# LCD-Input_Module.net
KiCad netlist of a schematic drawn in EAGLE
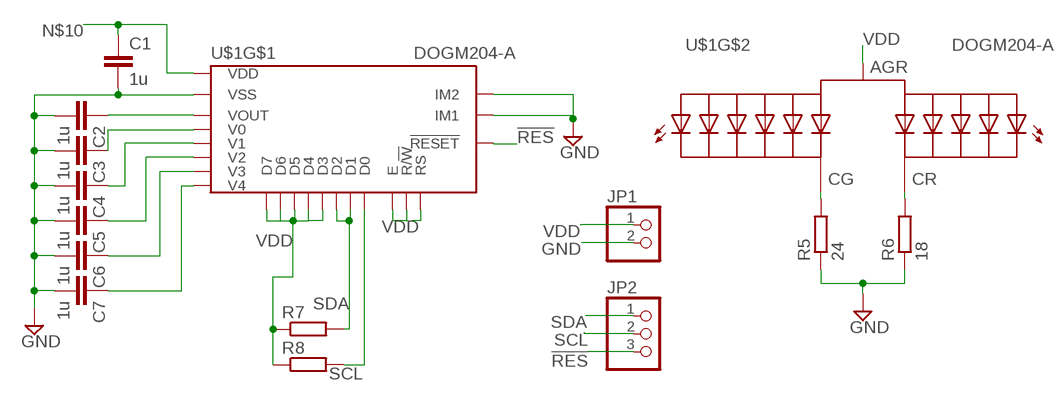
[diagram p0: schematic, sheet 1]
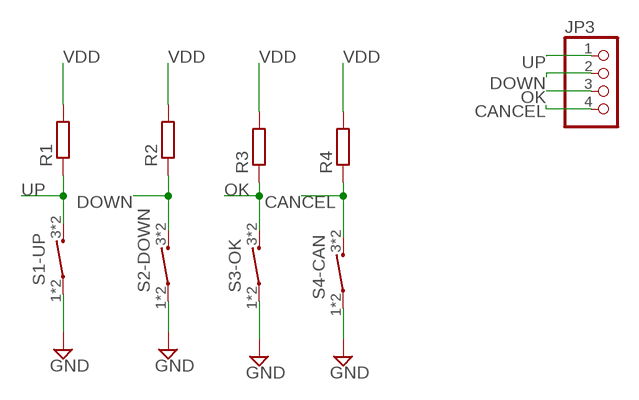
[diagram p1: schematic, sheet 2]

(export (version "E")
  (design (tool "Eeschema 10.0.6"))
  (components
    (comp (ref "JP3")
      (value "PINHD-1X4")
      (footprint "eagle-import:1X04")
      (libsource (lib "eagle-import") (part "PINHD-1X4"))
    )
    (comp (ref "R1")
      (value "R-EU_R0603")
      (footprint "eagle-import:R0603")
      (libsource (lib "eagle-import") (part "R-EU_R0603"))
    )
    (comp (ref "R2")
      (value "R-EU_R0603")
      (footprint "eagle-import:R0603")
      (libsource (lib "eagle-import") (part "R-EU_R0603"))
    )
    (comp (ref "R3")
      (value "R-EU_R0603")
      (footprint "eagle-import:R0603")
      (libsource (lib "eagle-import") (part "R-EU_R0603"))
    )
    (comp (ref "R4")
      (value "R-EU_R0603")
      (footprint "eagle-import:R0603")
      (libsource (lib "eagle-import") (part "R-EU_R0603"))
    )
    (comp (ref "S1-UP")
      (value "PTS647")
      (footprint "eagle-import:PTS647-TACTSWITCH")
      (libsource (lib "eagle-import") (part "PTS647"))
    )
    (comp (ref "S2-DOWN")
      (value "PTS647")
      (footprint "eagle-import:PTS647-TACTSWITCH")
      (libsource (lib "eagle-import") (part "PTS647"))
    )
    (comp (ref "S3-OK")
      (value "PTS647")
      (footprint "eagle-import:PTS647-TACTSWITCH")
      (libsource (lib "eagle-import") (part "PTS647"))
    )
    (comp (ref "S4-CAN")
      (value "PTS647")
      (footprint "eagle-import:PTS647-TACTSWITCH")
      (libsource (lib "eagle-import") (part "PTS647"))
    )
    (comp (ref "C1")
      (value "1u")
      (footprint "eagle-import:C0603")
      (libsource (lib "eagle-import") (part "C-EUC0603"))
    )
    (comp (ref "C2")
      (value "1u")
      (footprint "eagle-import:C0603")
      (libsource (lib "eagle-import") (part "C-EUC0603"))
    )
    (comp (ref "C3")
      (value "1u")
      (footprint "eagle-import:C0603")
      (libsource (lib "eagle-import") (part "C-EUC0603"))
    )
    (comp (ref "C4")
      (value "1u")
      (footprint "eagle-import:C0603")
      (libsource (lib "eagle-import") (part "C-EUC0603"))
    )
    (comp (ref "C5")
      (value "1u")
      (footprint "eagle-import:C0603")
      (libsource (lib "eagle-import") (part "C-EUC0603"))
    )
    (comp (ref "C6")
      (value "1u")
      (footprint "eagle-import:C0603")
      (libsource (lib "eagle-import") (part "C-EUC0603"))
    )
    (comp (ref "C7")
      (value "1u")
      (footprint "eagle-import:C0603")
      (libsource (lib "eagle-import") (part "C-EUC0603"))
    )
    (comp (ref "JP1")
      (value "PINHD-1X2")
      (footprint "eagle-import:1X02")
      (libsource (lib "eagle-import") (part "PINHD-1X2"))
    )
    (comp (ref "JP2")
      (value "PINHD-1X3")
      (footprint "eagle-import:1X03")
      (libsource (lib "eagle-import") (part "PINHD-1X3"))
    )
    (comp (ref "R5")
      (value "24")
      (footprint "eagle-import:R0603")
      (libsource (lib "eagle-import") (part "R-EU_R0603"))
    )
    (comp (ref "R6")
      (value "18")
      (footprint "eagle-import:R0603")
      (libsource (lib "eagle-import") (part "R-EU_R0603"))
    )
    (comp (ref "R7")
      (value "R-EU_R0603")
      (footprint "eagle-import:R0603")
      (libsource (lib "eagle-import") (part "R-EU_R0603"))
    )
    (comp (ref "R8")
      (value "R-EU_R0603")
      (footprint "eagle-import:R0603")
      (libsource (lib "eagle-import") (part "R-EU_R0603"))
    )
    (comp (ref "U$1")
      (value "DOGM204-A")
      (footprint "eagle-import:LCD")
      (libsource (lib "eagle-import") (part "DOGM204-A"))
    )
  )
  (nets
    (net (code "1") (name "CANCEL") (class "Default")
      (node (ref "JP3") (pin "4") (pinfunction "4_4") (pintype "passive"))
      (node (ref "R4") (pin "1") (pinfunction "1_1") (pintype "passive"))
      (node (ref "S4-CAN") (pin "3") (pinfunction "2_3") (pintype "passive"))
      (node (ref "S4-CAN") (pin "4") (pinfunction "2_4") (pintype "passive"))
    )
    (net (code "2") (name "DOWN") (class "Default")
      (node (ref "JP3") (pin "2") (pinfunction "2_2") (pintype "passive"))
      (node (ref "R2") (pin "1") (pinfunction "1_1") (pintype "passive"))
      (node (ref "S2-DOWN") (pin "3") (pinfunction "2_3") (pintype "passive"))
      (node (ref "S2-DOWN") (pin "4") (pinfunction "2_4") (pintype "passive"))
    )
    (net (code "3") (name "GND") (class "Default")
      (node (ref "C1") (pin "2") (pinfunction "2_2") (pintype "passive"))
      (node (ref "C2") (pin "2") (pinfunction "2_2") (pintype "passive"))
      (node (ref "C3") (pin "2") (pinfunction "2_2") (pintype "passive"))
      (node (ref "C4") (pin "2") (pinfunction "2_2") (pintype "passive"))
      (node (ref "C5") (pin "2") (pinfunction "2_2") (pintype "passive"))
      (node (ref "C6") (pin "2") (pinfunction "2_2") (pintype "passive"))
      (node (ref "C7") (pin "2") (pinfunction "2_2") (pintype "passive"))
      (node (ref "JP1") (pin "2") (pinfunction "2_2") (pintype "passive"))
      (node (ref "R5") (pin "1") (pinfunction "1_1") (pintype "passive"))
      (node (ref "R6") (pin "1") (pinfunction "1_1") (pintype "passive"))
      (node (ref "S1-UP") (pin "1") (pinfunction "1_1") (pintype "passive"))
      (node (ref "S1-UP") (pin "2") (pinfunction "1_2") (pintype "passive"))
      (node (ref "S2-DOWN") (pin "1") (pinfunction "1_1") (pintype "passive"))
      (node (ref "S2-DOWN") (pin "2") (pinfunction "1_2") (pintype "passive"))
      (node (ref "S3-OK") (pin "1") (pinfunction "1_1") (pintype "passive"))
      (node (ref "S3-OK") (pin "2") (pinfunction "1_2") (pintype "passive"))
      (node (ref "S4-CAN") (pin "1") (pinfunction "1_1") (pintype "passive"))
      (node (ref "S4-CAN") (pin "2") (pinfunction "1_2") (pintype "passive"))
      (node (ref "U$1") (pin "P$29") (pinfunction "IM2_P$29") (pintype "bidirectional"))
      (node (ref "U$1") (pin "P$30") (pinfunction "IM1_P$30") (pintype "bidirectional"))
      (node (ref "U$1") (pin "P$32") (pinfunction "VSS_P$32") (pintype "bidirectional"))
    )
    (net (code "4") (name "N$10") (class "Default")
      (node (ref "C1") (pin "1") (pinfunction "1_1") (pintype "passive"))
      (node (ref "U$1") (pin "P$31") (pinfunction "VDD_P$31") (pintype "bidirectional"))
    )
    (net (code "5") (name "Net-(U$1A-V0)") (class "Default")
      (node (ref "C3") (pin "1") (pinfunction "1_1") (pintype "passive"))
      (node (ref "U$1") (pin "P$24") (pinfunction "V0_P$24") (pintype "bidirectional"))
    )
    (net (code "6") (name "Net-(U$1A-V1)") (class "Default")
      (node (ref "C4") (pin "1") (pinfunction "1_1") (pintype "passive"))
      (node (ref "U$1") (pin "P$25") (pinfunction "V1_P$25") (pintype "bidirectional"))
    )
    (net (code "7") (name "Net-(U$1A-V2)") (class "Default")
      (node (ref "C5") (pin "1") (pinfunction "1_1") (pintype "passive"))
      (node (ref "U$1") (pin "P$26") (pinfunction "V2_P$26") (pintype "bidirectional"))
    )
    (net (code "8") (name "Net-(U$1A-V3)") (class "Default")
      (node (ref "C6") (pin "1") (pinfunction "1_1") (pintype "passive"))
      (node (ref "U$1") (pin "P$27") (pinfunction "V3_P$27") (pintype "bidirectional"))
    )
    (net (code "9") (name "Net-(U$1A-V4)") (class "Default")
      (node (ref "C7") (pin "1") (pinfunction "1_1") (pintype "passive"))
      (node (ref "U$1") (pin "P$28") (pinfunction "V4_P$28") (pintype "bidirectional"))
    )
    (net (code "10") (name "Net-(U$1A-VOUT)") (class "Default")
      (node (ref "C2") (pin "1") (pinfunction "1_1") (pintype "passive"))
      (node (ref "U$1") (pin "P$23") (pinfunction "VOUT_P$23") (pintype "bidirectional"))
    )
    (net (code "11") (name "Net-(U$1B-CG)") (class "Default")
      (node (ref "R5") (pin "2") (pinfunction "2_2") (pintype "passive"))
      (node (ref "U$1") (pin "P$21") (pinfunction "CG_P$21") (pintype "passive"))
    )
    (net (code "12") (name "Net-(U$1B-CR)") (class "Default")
      (node (ref "R6") (pin "2") (pinfunction "2_2") (pintype "passive"))
      (node (ref "U$1") (pin "P$22") (pinfunction "CR_P$22") (pintype "passive"))
    )
    (net (code "13") (name "OK") (class "Default")
      (node (ref "JP3") (pin "3") (pinfunction "3_3") (pintype "passive"))
      (node (ref "R3") (pin "1") (pinfunction "1_1") (pintype "passive"))
      (node (ref "S3-OK") (pin "3") (pinfunction "2_3") (pintype "passive"))
      (node (ref "S3-OK") (pin "4") (pinfunction "2_4") (pintype "passive"))
    )
    (net (code "14") (name "SCL") (class "Default")
      (node (ref "JP2") (pin "2") (pinfunction "2_2") (pintype "passive"))
      (node (ref "R8") (pin "2") (pinfunction "2_2") (pintype "passive"))
      (node (ref "U$1") (pin "P$40") (pinfunction "D0_P$40") (pintype "bidirectional"))
    )
    (net (code "15") (name "SDA") (class "Default")
      (node (ref "JP2") (pin "1") (pinfunction "1_1") (pintype "passive"))
      (node (ref "R7") (pin "2") (pinfunction "2_2") (pintype "passive"))
      (node (ref "U$1") (pin "P$38") (pinfunction "D2_P$38") (pintype "bidirectional"))
      (node (ref "U$1") (pin "P$39") (pinfunction "D1_P$39") (pintype "bidirectional"))
    )
    (net (code "16") (name "UP") (class "Default")
      (node (ref "JP3") (pin "1") (pinfunction "1_1") (pintype "passive"))
      (node (ref "R1") (pin "1") (pinfunction "1_1") (pintype "passive"))
      (node (ref "S1-UP") (pin "3") (pinfunction "2_3") (pintype "passive"))
      (node (ref "S1-UP") (pin "4") (pinfunction "2_4") (pintype "passive"))
    )
    (net (code "17") (name "VDD") (class "Default")
      (node (ref "JP1") (pin "1") (pinfunction "1_1") (pintype "passive"))
      (node (ref "R1") (pin "2") (pinfunction "2_2") (pintype "passive"))
      (node (ref "R2") (pin "2") (pinfunction "2_2") (pintype "passive"))
      (node (ref "R3") (pin "2") (pinfunction "2_2") (pintype "passive"))
      (node (ref "R4") (pin "2") (pinfunction "2_2") (pintype "passive"))
      (node (ref "R7") (pin "1") (pinfunction "1_1") (pintype "passive"))
      (node (ref "R8") (pin "1") (pinfunction "1_1") (pintype "passive"))
      (node (ref "U$1") (pin "P$1") (pinfunction "AGR_P$1") (pintype "passive"))
      (node (ref "U$1") (pin "P$33") (pinfunction "D7_P$33") (pintype "bidirectional"))
      (node (ref "U$1") (pin "P$34") (pinfunction "D6_P$34") (pintype "bidirectional"))
      (node (ref "U$1") (pin "P$35") (pinfunction "D5_P$35") (pintype "bidirectional"))
      (node (ref "U$1") (pin "P$36") (pinfunction "D4_P$36") (pintype "bidirectional"))
      (node (ref "U$1") (pin "P$37") (pinfunction "D3_P$37") (pintype "bidirectional"))
      (node (ref "U$1") (pin "P$41") (pinfunction "E_P$41") (pintype "bidirectional"))
      (node (ref "U$1") (pin "P$42") (pinfunction "R/~{W}_P$42") (pintype "bidirectional"))
      (node (ref "U$1") (pin "P$43") (pinfunction "RS_P$43") (pintype "bidirectional"))
    )
    (net (code "18") (name "~{RES}") (class "Default")
      (node (ref "JP2") (pin "3") (pinfunction "3_3") (pintype "passive"))
      (node (ref "U$1") (pin "P$44") (pinfunction "~{RESET}_P$44") (pintype "bidirectional"))
    )
  )
)
